# small_tv.net
KiCad netlist of a schematic drawn in EasyEDA Pro
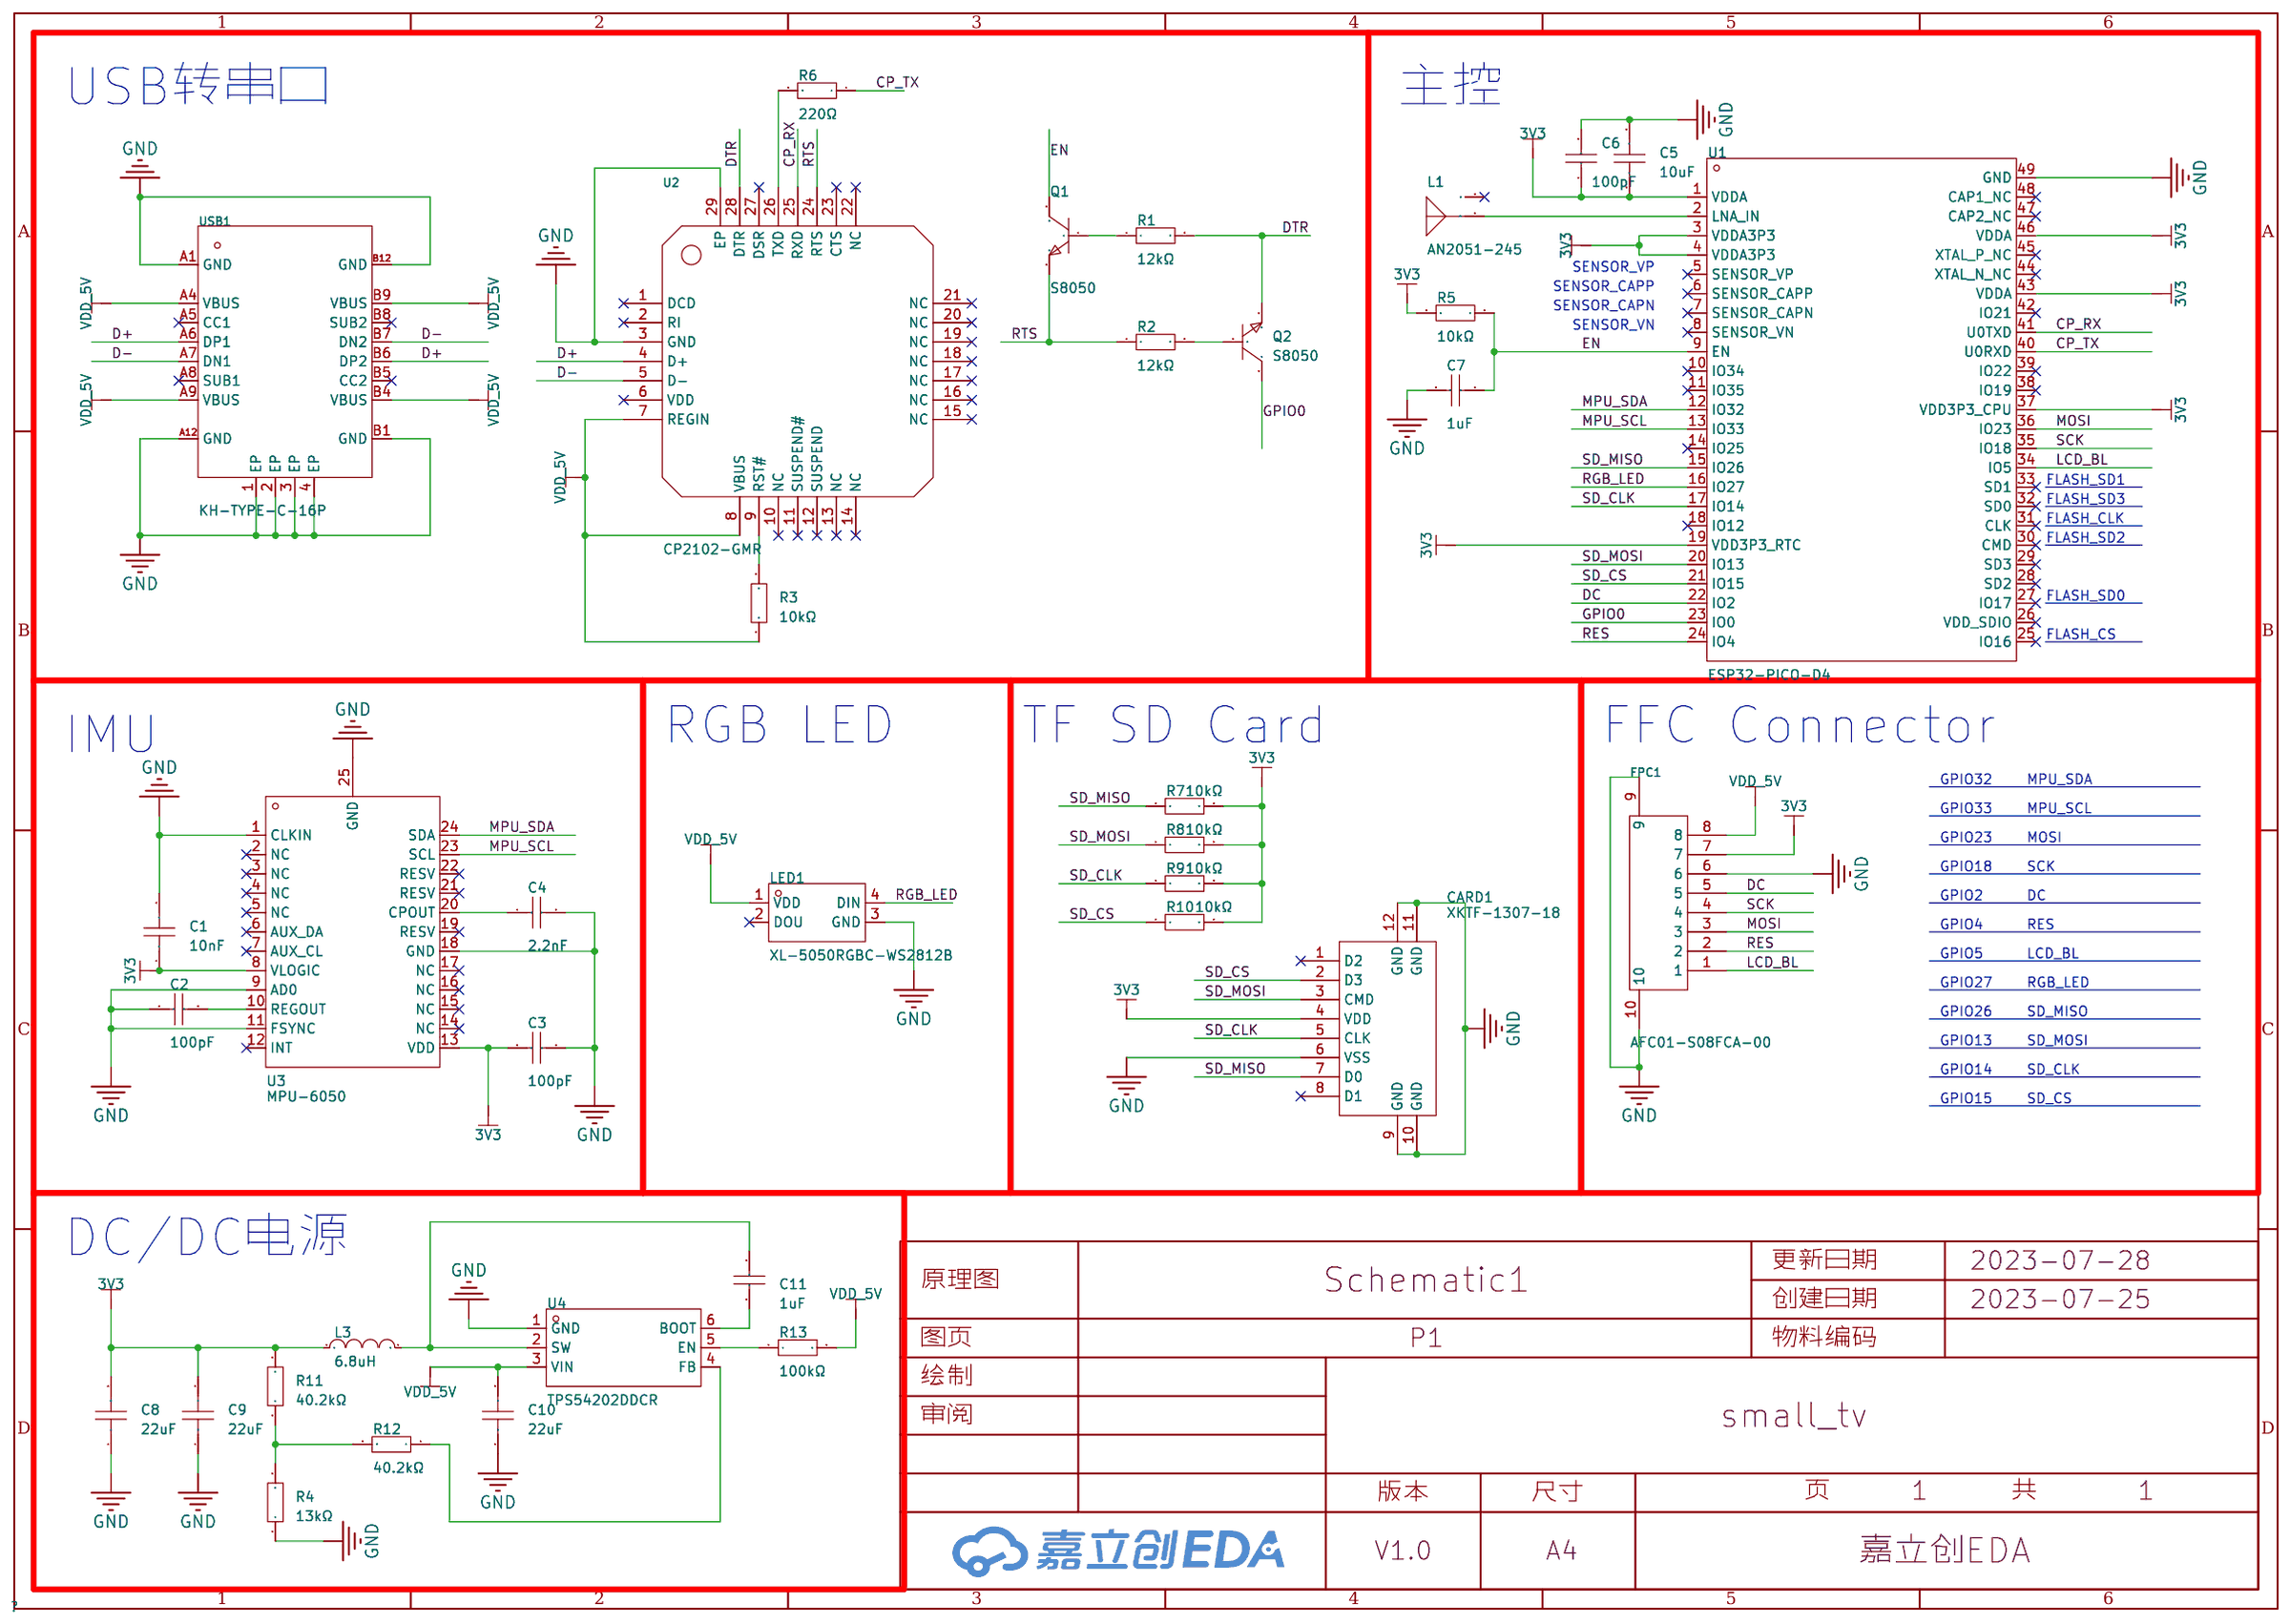
[diagram p0: schematic sheet]

(export (version "E")
  (design (tool "Eeschema 10.0.6"))
  (components
    (comp (ref "C1")
      (value "10nF")
      (footprint "easyedapro:C0603")
      (description "容值:10uF;精度:±10%;额定电压:10V;材质(温度系数):X5R;")
      (fields
        (field (name "Manufacturer Part") "CL10A106KP8NNNC")
        (field (name "Manufacturer") "SAMSUNG(三星)")
      )
      (libsource (lib "easyedapro") (part "CL10A106KP8NNNC"))
    )
    (comp (ref "C2")
      (value "100pF")
      (footprint "easyedapro:C0603")
      (description "容值:100pF;精度:±5%;额定电压:50V;材质(温度系数):C0G;")
      (fields
        (field (name "Manufacturer Part") "CL10C101JB8NNNC")
        (field (name "Manufacturer") "SAMSUNG(三星)")
      )
      (libsource (lib "easyedapro") (part "CL10C101JB8NNNC"))
    )
    (comp (ref "C3")
      (value "100pF")
      (footprint "easyedapro:C0603")
      (description "容值:100pF;精度:±5%;额定电压:50V;材质(温度系数):C0G;")
      (fields
        (field (name "Manufacturer Part") "CL10C101JB8NNNC")
        (field (name "Manufacturer") "SAMSUNG(三星)")
      )
      (libsource (lib "easyedapro") (part "CL10C101JB8NNNC"))
    )
    (comp (ref "C4")
      (value "2.2nF")
      (footprint "easyedapro:C0603")
      (description "容值:2.2nF;精度:±5%;额定电压:50V;材质(温度系数):NP0;")
      (fields
        (field (name "Manufacturer Part") "CC0603JRNPO9BN222")
        (field (name "Manufacturer") "YAGEO(国巨)")
      )
      (libsource (lib "easyedapro") (part "CC0603JRNPO9BN222"))
    )
    (comp (ref "C5")
      (value "10uF")
      (footprint "easyedapro:C0603")
      (description "容值:10uF;精度:±10%;额定电压:10V;材质(温度系数):X5R;")
      (fields
        (field (name "Manufacturer Part") "CL10A106KP8NNNC")
        (field (name "Manufacturer") "SAMSUNG(三星)")
      )
      (libsource (lib "easyedapro") (part "CL10A106KP8NNNC"))
    )
    (comp (ref "C6")
      (value "100pF")
      (footprint "easyedapro:C0603")
      (description "容值:100pF;精度:±5%;额定电压:50V;材质(温度系数):C0G;")
      (fields
        (field (name "Manufacturer Part") "CL10C101JB8NNNC")
        (field (name "Manufacturer") "SAMSUNG(三星)")
      )
      (libsource (lib "easyedapro") (part "CL10C101JB8NNNC"))
    )
    (comp (ref "C7")
      (value "1uF")
      (footprint "easyedapro:C0603")
      (description "容值:1uF;精度:±10%;额定电压:50V;材质(温度系数):X5R;")
      (fields
        (field (name "Manufacturer Part") "CL10A105KB8NNNC")
        (field (name "Manufacturer") "SAMSUNG(三星)")
      )
      (libsource (lib "easyedapro") (part "CL10A105KB8NNNC"))
    )
    (comp (ref "C8")
      (value "22uF")
      (footprint "easyedapro:C0603")
      (description "容值:22uF;精度:±20%;额定电压:10V;材质(温度系数):X5R;")
      (fields
        (field (name "Manufacturer Part") "CL10A226MP8NUNE")
        (field (name "Manufacturer") "SAMSUNG(三星)")
      )
      (libsource (lib "easyedapro") (part "CL10A226MP8NUNE"))
    )
    (comp (ref "C9")
      (value "22uF")
      (footprint "easyedapro:C0603")
      (description "容值:22uF;精度:±20%;额定电压:10V;材质(温度系数):X5R;")
      (fields
        (field (name "Manufacturer Part") "CL10A226MP8NUNE")
        (field (name "Manufacturer") "SAMSUNG(三星)")
      )
      (libsource (lib "easyedapro") (part "CL10A226MP8NUNE"))
    )
    (comp (ref "C10")
      (value "22uF")
      (footprint "easyedapro:C0603")
      (description "容值:22uF;精度:±20%;额定电压:10V;材质(温度系数):X5R;")
      (fields
        (field (name "Manufacturer Part") "CL10A226MP8NUNE")
        (field (name "Manufacturer") "SAMSUNG(三星)")
      )
      (libsource (lib "easyedapro") (part "CL10A226MP8NUNE"))
    )
    (comp (ref "C11")
      (value "1uF")
      (footprint "easyedapro:C0603")
      (description "容值:1uF;精度:±10%;额定电压:50V;材质(温度系数):X5R;")
      (fields
        (field (name "Manufacturer Part") "CL10A105KB8NNNC")
        (field (name "Manufacturer") "SAMSUNG(三星)")
      )
      (libsource (lib "easyedapro") (part "CL10A105KB8NNNC"))
    )
    (comp (ref "CARD1")
      (value "XKTF-1307-18")
      (footprint "easyedapro:TF-SMD_XKTF-1307-18")
      (fields (field (name "Manufacturer") "XKB Connectivity(中国星坤)"))
      (libsource (lib "easyedapro") (part "XKTF-1307-18"))
    )
    (comp (ref "FPC1")
      (value "AFC01-S08FCA-00")
      (footprint "easyedapro:FPC-SMD_P0.50-8P_FGS-XJ-H2.0")
      (description "间距:0.5mm;触点数量:8P;锁定特性:翻盖式;安装类型:卧贴;触点类型:下接;")
      (fields (field (name "Manufacturer") "JS(钜硕电子)"))
      (libsource (lib "easyedapro") (part "AFC01-S08FCA-00"))
    )
    (comp (ref "L1")
      (value "AN2051-245")
      (footprint "easyedapro:ANT2051")
      (description "小体积，高增益，WIFI，蓝牙，zigBee 2.4G天线")
      (fields (field (name "Manufacturer") "rainsun(霖昱微)"))
      (libsource (lib "easyedapro") (part "AN2051-245"))
    )
    (comp (ref "L3")
      (value "6.8uH")
      (footprint "easyedapro:IND-SMD_L4.4-W4.2")
      (description "电感值:6.8uH;精度:±20%;额定电流:2.4A;饱和电流(Isat):2.5A;")
      (fields (field (name "Manufacturer Part") "FXL0420-6R8-M") (field (name "Manufacturer") "cjiang(长江微电)"))
      (libsource (lib "easyedapro") (part "FXL0420-6R8-M"))
    )
    (comp (ref "LED1")
      (value "XL-5050RGBC-WS2812B")
      (footprint "easyedapro:LED-SMD_4P-L5.0-W5.0-BL_XL-5050RGBC")
      (description "发光颜色:RGB三色;二极管配置:-;主波长:-;色温:-;功率:-;安装方式:正贴;")
      (fields (field (name "Manufacturer") "XINGLIGHT(成兴光)"))
      (libsource (lib "easyedapro") (part "XL-5050RGBC-WS2812B"))
    )
    (comp (ref "Q1")
      (value "S8050")
      (footprint "easyedapro:SOT-23-3_L2.9-W1.6-P1.90-LS2.8-BR")
      (description "晶体管类型:NPN;集射极击穿电压(Vceo):25V;集电极电流(Ic):500mA;功率(Pd):300mW;直流电流增益(hFE@Ic,Vce):120@50mA,1V;")
      (fields (field (name "Manufacturer") "CJ(江苏长电/长晶)"))
      (libsource (lib "easyedapro") (part "S8050_C105433"))
    )
    (comp (ref "Q2")
      (value "S8050")
      (footprint "easyedapro:SOT-23-3_L2.9-W1.6-P1.90-LS2.8-BR")
      (description "晶体管类型:NPN;集射极击穿电压(Vceo):25V;集电极电流(Ic):500mA;功率(Pd):300mW;直流电流增益(hFE@Ic,Vce):120@50mA,1V;")
      (fields (field (name "Manufacturer") "CJ(江苏长电/长晶)"))
      (libsource (lib "easyedapro") (part "S8050_C105433"))
    )
    (comp (ref "R1")
      (value "12kΩ")
      (footprint "easyedapro:R0603")
      (description "电阻类型:厚膜电阻;阻值:12kΩ;精度:±1%;功率:100mW;")
      (fields
        (field (name "Manufacturer Part") "0603WAF1202T5E")
        (field (name "Manufacturer") "UNI-ROYAL(厚声)")
      )
      (libsource (lib "easyedapro") (part "0603WAF1202T5E"))
    )
    (comp (ref "R2")
      (value "12kΩ")
      (footprint "easyedapro:R0603")
      (description "电阻类型:厚膜电阻;阻值:12kΩ;精度:±1%;功率:100mW;")
      (fields
        (field (name "Manufacturer Part") "0603WAF1202T5E")
        (field (name "Manufacturer") "UNI-ROYAL(厚声)")
      )
      (libsource (lib "easyedapro") (part "0603WAF1202T5E"))
    )
    (comp (ref "R3")
      (value "10kΩ")
      (footprint "easyedapro:R0603")
      (description "电阻类型:厚膜电阻;阻值:10kΩ;精度:±1%;功率:100mW;")
      (fields
        (field (name "Manufacturer Part") "0603WAF1002T5E")
        (field (name "Manufacturer") "UNI-ROYAL(厚声)")
      )
      (libsource (lib "easyedapro") (part "0603WAF1002T5E"))
    )
    (comp (ref "R4")
      (value "13kΩ")
      (footprint "easyedapro:R0603")
      (description "电阻类型:厚膜电阻;阻值:13kΩ;精度:±1%;功率:100mW;")
      (fields
        (field (name "Manufacturer Part") "0603WAF1302T5E")
        (field (name "Manufacturer") "UNI-ROYAL(厚声)")
      )
      (libsource (lib "easyedapro") (part "0603WAF1302T5E"))
    )
    (comp (ref "R5")
      (value "10kΩ")
      (footprint "easyedapro:R0603")
      (description "电阻类型:厚膜电阻;阻值:10kΩ;精度:±1%;功率:100mW;")
      (fields
        (field (name "Manufacturer Part") "0603WAF1002T5E")
        (field (name "Manufacturer") "UNI-ROYAL(厚声)")
      )
      (libsource (lib "easyedapro") (part "0603WAF1002T5E"))
    )
    (comp (ref "R6")
      (value "220Ω")
      (footprint "easyedapro:R0603")
      (description "电阻类型:厚膜电阻;阻值:220Ω;精度:±1%;功率:100mW;")
      (fields
        (field (name "Manufacturer Part") "0603WAF2200T5E")
        (field (name "Manufacturer") "UNI-ROYAL(厚声)")
      )
      (libsource (lib "easyedapro") (part "0603WAF2200T5E"))
    )
    (comp (ref "R7")
      (value "10kΩ")
      (footprint "easyedapro:R0603")
      (description "电阻类型:厚膜电阻;阻值:10kΩ;精度:±1%;功率:100mW;")
      (fields
        (field (name "Manufacturer Part") "0603WAF1002T5E")
        (field (name "Manufacturer") "UNI-ROYAL(厚声)")
      )
      (libsource (lib "easyedapro") (part "0603WAF1002T5E"))
    )
    (comp (ref "R8")
      (value "10kΩ")
      (footprint "easyedapro:R0603")
      (description "电阻类型:厚膜电阻;阻值:10kΩ;精度:±1%;功率:100mW;")
      (fields
        (field (name "Manufacturer Part") "0603WAF1002T5E")
        (field (name "Manufacturer") "UNI-ROYAL(厚声)")
      )
      (libsource (lib "easyedapro") (part "0603WAF1002T5E"))
    )
    (comp (ref "R9")
      (value "10kΩ")
      (footprint "easyedapro:R0603")
      (description "电阻类型:厚膜电阻;阻值:10kΩ;精度:±1%;功率:100mW;")
      (fields
        (field (name "Manufacturer Part") "0603WAF1002T5E")
        (field (name "Manufacturer") "UNI-ROYAL(厚声)")
      )
      (libsource (lib "easyedapro") (part "0603WAF1002T5E"))
    )
    (comp (ref "R10")
      (value "10kΩ")
      (footprint "easyedapro:R0603")
      (description "电阻类型:厚膜电阻;阻值:10kΩ;精度:±1%;功率:100mW;")
      (fields
        (field (name "Manufacturer Part") "0603WAF1002T5E")
        (field (name "Manufacturer") "UNI-ROYAL(厚声)")
      )
      (libsource (lib "easyedapro") (part "0603WAF1002T5E"))
    )
    (comp (ref "R11")
      (value "40.2kΩ")
      (footprint "easyedapro:R0603")
      (description "电阻类型:厚膜电阻;阻值:40.2kΩ;精度:±1%;功率:100mW;")
      (fields
        (field (name "Manufacturer Part") "0603WAF4022T5E")
        (field (name "Manufacturer") "UNI-ROYAL(厚声)")
      )
      (libsource (lib "easyedapro") (part "0603WAF4022T5E"))
    )
    (comp (ref "R12")
      (value "40.2kΩ")
      (footprint "easyedapro:R0603")
      (description "电阻类型:厚膜电阻;阻值:40.2kΩ;精度:±1%;功率:100mW;")
      (fields
        (field (name "Manufacturer Part") "0603WAF4022T5E")
        (field (name "Manufacturer") "UNI-ROYAL(厚声)")
      )
      (libsource (lib "easyedapro") (part "0603WAF4022T5E"))
    )
    (comp (ref "R13")
      (value "100kΩ")
      (footprint "easyedapro:R0603")
      (description "电阻类型:厚膜电阻;阻值:100kΩ;精度:±1%;功率:100mW;")
      (fields
        (field (name "Manufacturer Part") "0603WAF1003T5E")
        (field (name "Manufacturer") "UNI-ROYAL(厚声)")
      )
      (libsource (lib "easyedapro") (part "0603WAF1003T5E"))
    )
    (comp (ref "U1")
      (value "ESP32-PICO-D4")
      (footprint "easyedapro:LGA-48_L7.0-W7.0-P0.50-BL-EP5.4")
      (fields (field (name "Manufacturer") "ESPRESSIF(乐鑫)"))
      (libsource (lib "easyedapro") (part "ESP32-PICO-D4"))
    )
    (comp (ref "U2")
      (value "CP2102-GMR")
      (footprint "easyedapro:WQFN-28_L5.0-W5.0-P0.50-BL-EP3.2")
      (description "应用功能:收发器;接口协议:USB;数据速率:1Mbps;")
      (fields (field (name "Manufacturer") "SILICON LABS(芯科)"))
      (libsource (lib "easyedapro") (part "CP2102-GMR"))
    )
    (comp (ref "U3")
      (value "MPU-6050")
      (footprint "easyedapro:QFN-24_L4.0-W4.0-P0.50-BL-EP2.7")
      (description "三轴加速度计和三轴陀螺仪，工作电压：2.375V~3.46V")
      (fields (field (name "Manufacturer") "TDK InvenSense(应美盛)"))
      (libsource (lib "easyedapro") (part "MPU-6050_C24112"))
    )
    (comp (ref "U4")
      (value "TPS54202DDCR")
      (footprint "easyedapro:SOT-23-6_L2.9-W1.6-P0.95-LS2.8-BL")
      (description "可输出电流:2A;开关工作频率:500kHz;输出类型:Adjustable;输出电压的路数:1;功能类型:Step-Down;输出配置:Positive;")
      (fields (field (name "Manufacturer") "TI(德州仪器)"))
      (libsource (lib "easyedapro") (part "TPS54202DDCR"))
    )
    (comp (ref "USB1")
      (value "KH-TYPE-C-16P")
      (footprint "easyedapro:USB-C-SMD_KH-TYPE-C-16P")
      (description "Type-C母座 16PIN 立式四角贴板无压片")
      (fields (field (name "Manufacturer") "kinghelm(金航标)"))
      (libsource (lib "easyedapro") (part "KH-TYPE-C-16P"))
    )
  )
  (nets
    (net (code "1") (name "/CP_RX") (class "Default")
      (node (ref "U1") (pin "41") (pinfunction "U0TXD_41") (pintype "input"))
      (node (ref "U2") (pin "25") (pinfunction "RXD_25") (pintype "input"))
    )
    (net (code "2") (name "/CP_TX") (class "Default")
      (node (ref "R6") (pin "1") (pinfunction "1_1") (pintype "input"))
      (node (ref "U1") (pin "40") (pinfunction "U0RXD_40") (pintype "input"))
    )
    (net (code "3") (name "/D+") (class "Default")
      (node (ref "U2") (pin "4") (pinfunction "D+_4") (pintype "input"))
      (node (ref "USB1") (pin "A6") (pinfunction "DP1_A6") (pintype "input"))
      (node (ref "USB1") (pin "B6") (pinfunction "DP2_B6") (pintype "input"))
    )
    (net (code "4") (name "/D-") (class "Default")
      (node (ref "U2") (pin "5") (pinfunction "D-_5") (pintype "input"))
      (node (ref "USB1") (pin "A7") (pinfunction "DN1_A7") (pintype "input"))
      (node (ref "USB1") (pin "B7") (pinfunction "DN2_B7") (pintype "input"))
    )
    (net (code "5") (name "/DC") (class "Default")
      (node (ref "FPC1") (pin "5") (pinfunction "5_5") (pintype "input"))
      (node (ref "U1") (pin "22") (pinfunction "IO2_22") (pintype "input"))
    )
    (net (code "6") (name "/DTR") (class "Default")
      (node (ref "Q2") (pin "2") (pinfunction "2_2") (pintype "input"))
      (node (ref "R1") (pin "2") (pinfunction "2_2") (pintype "input"))
      (node (ref "U2") (pin "28") (pinfunction "DTR_28") (pintype "input"))
    )
    (net (code "7") (name "/EN") (class "Default")
      (node (ref "C7") (pin "1") (pinfunction "1_1") (pintype "input"))
      (node (ref "Q1") (pin "3") (pinfunction "3_3") (pintype "input"))
      (node (ref "R5") (pin "1") (pinfunction "1_1") (pintype "input"))
      (node (ref "U1") (pin "9") (pinfunction "EN_9") (pintype "input"))
    )
    (net (code "8") (name "/GPIO0") (class "Default")
      (node (ref "Q2") (pin "3") (pinfunction "3_3") (pintype "input"))
      (node (ref "U1") (pin "23") (pinfunction "IO0_23") (pintype "input"))
    )
    (net (code "9") (name "/LCD_BL") (class "Default")
      (node (ref "FPC1") (pin "1") (pinfunction "1_1") (pintype "input"))
      (node (ref "U1") (pin "34") (pinfunction "IO5_34") (pintype "input"))
    )
    (net (code "10") (name "/MOSI") (class "Default")
      (node (ref "FPC1") (pin "3") (pinfunction "3_3") (pintype "input"))
      (node (ref "U1") (pin "36") (pinfunction "IO23_36") (pintype "input"))
    )
    (net (code "11") (name "/MPU_SCL") (class "Default")
      (node (ref "U1") (pin "13") (pinfunction "IO33_13") (pintype "input"))
      (node (ref "U3") (pin "23") (pinfunction "SCL_23") (pintype "input"))
    )
    (net (code "12") (name "/MPU_SDA") (class "Default")
      (node (ref "U1") (pin "12") (pinfunction "IO32_12") (pintype "input"))
      (node (ref "U3") (pin "24") (pinfunction "SDA_24") (pintype "input"))
    )
    (net (code "13") (name "/RES") (class "Default")
      (node (ref "FPC1") (pin "2") (pinfunction "2_2") (pintype "input"))
      (node (ref "U1") (pin "24") (pinfunction "IO4_24") (pintype "input"))
    )
    (net (code "14") (name "/RGB_LED") (class "Default")
      (node (ref "LED1") (pin "4") (pinfunction "DIN_4") (pintype "input"))
      (node (ref "U1") (pin "16") (pinfunction "IO27_16") (pintype "input"))
    )
    (net (code "15") (name "/RTS") (class "Default")
      (node (ref "Q1") (pin "2") (pinfunction "2_2") (pintype "input"))
      (node (ref "R2") (pin "1") (pinfunction "1_1") (pintype "input"))
      (node (ref "U2") (pin "24") (pinfunction "RTS_24") (pintype "input"))
    )
    (net (code "16") (name "/SCK") (class "Default")
      (node (ref "FPC1") (pin "4") (pinfunction "4_4") (pintype "input"))
      (node (ref "U1") (pin "35") (pinfunction "IO18_35") (pintype "input"))
    )
    (net (code "17") (name "/SD_CLK") (class "Default")
      (node (ref "CARD1") (pin "5") (pinfunction "CLK_5") (pintype "input"))
      (node (ref "R9") (pin "1") (pinfunction "1_1") (pintype "input"))
      (node (ref "U1") (pin "17") (pinfunction "IO14_17") (pintype "input"))
    )
    (net (code "18") (name "/SD_CS") (class "Default")
      (node (ref "CARD1") (pin "2") (pinfunction "D3_2") (pintype "input"))
      (node (ref "R10") (pin "1") (pinfunction "1_1") (pintype "input"))
      (node (ref "U1") (pin "21") (pinfunction "IO15_21") (pintype "input"))
    )
    (net (code "19") (name "/SD_MISO") (class "Default")
      (node (ref "CARD1") (pin "7") (pinfunction "D0_7") (pintype "input"))
      (node (ref "R7") (pin "1") (pinfunction "1_1") (pintype "input"))
      (node (ref "U1") (pin "15") (pinfunction "IO26_15") (pintype "input"))
    )
    (net (code "20") (name "/SD_MOSI") (class "Default")
      (node (ref "CARD1") (pin "3") (pinfunction "CMD_3") (pintype "input"))
      (node (ref "R8") (pin "1") (pinfunction "1_1") (pintype "input"))
      (node (ref "U1") (pin "20") (pinfunction "IO13_20") (pintype "input"))
    )
    (net (code "21") (name "3V3") (class "Default")
      (node (ref "C1") (pin "1") (pinfunction "1_1") (pintype "input"))
      (node (ref "C3") (pin "1") (pinfunction "1_1") (pintype "input"))
      (node (ref "C5") (pin "1") (pinfunction "1_1") (pintype "input"))
      (node (ref "C6") (pin "1") (pinfunction "1_1") (pintype "input"))
      (node (ref "C8") (pin "2") (pinfunction "2_2") (pintype "input"))
      (node (ref "C9") (pin "2") (pinfunction "2_2") (pintype "input"))
      (node (ref "CARD1") (pin "4") (pinfunction "VDD_4") (pintype "input"))
      (node (ref "FPC1") (pin "7") (pinfunction "7_7") (pintype "input"))
      (node (ref "L3") (pin "1") (pinfunction "1_1") (pintype "input"))
      (node (ref "R10") (pin "2") (pinfunction "2_2") (pintype "input"))
      (node (ref "R11") (pin "2") (pinfunction "2_2") (pintype "input"))
      (node (ref "R5") (pin "2") (pinfunction "2_2") (pintype "input"))
      (node (ref "R7") (pin "2") (pinfunction "2_2") (pintype "input"))
      (node (ref "R8") (pin "2") (pinfunction "2_2") (pintype "input"))
      (node (ref "R9") (pin "2") (pinfunction "2_2") (pintype "input"))
      (node (ref "U1") (pin "1") (pinfunction "VDDA_1") (pintype "input"))
      (node (ref "U1") (pin "19") (pinfunction "VDD3P3_RTC_19") (pintype "input"))
      (node (ref "U1") (pin "3") (pinfunction "VDDA3P3_3") (pintype "input"))
      (node (ref "U1") (pin "37") (pinfunction "VDD3P3_CPU_37") (pintype "input"))
      (node (ref "U1") (pin "4") (pinfunction "VDDA3P3_4") (pintype "input"))
      (node (ref "U1") (pin "43") (pinfunction "VDDA_43") (pintype "input"))
      (node (ref "U1") (pin "46") (pinfunction "VDDA_46") (pintype "input"))
      (node (ref "U3") (pin "13") (pinfunction "VDD_13") (pintype "input"))
      (node (ref "U3") (pin "8") (pinfunction "VLOGIC_8") (pintype "input"))
    )
    (net (code "22") (name "GND") (class "Default")
      (node (ref "C1") (pin "2") (pinfunction "2_2") (pintype "input"))
      (node (ref "C10") (pin "1") (pinfunction "1_1") (pintype "input"))
      (node (ref "C2") (pin "1") (pinfunction "1_1") (pintype "input"))
      (node (ref "C3") (pin "2") (pinfunction "2_2") (pintype "input"))
      (node (ref "C4") (pin "2") (pinfunction "2_2") (pintype "input"))
      (node (ref "C5") (pin "2") (pinfunction "2_2") (pintype "input"))
      (node (ref "C6") (pin "2") (pinfunction "2_2") (pintype "input"))
      (node (ref "C7") (pin "2") (pinfunction "2_2") (pintype "input"))
      (node (ref "C8") (pin "1") (pinfunction "1_1") (pintype "input"))
      (node (ref "C9") (pin "1") (pinfunction "1_1") (pintype "input"))
      (node (ref "CARD1") (pin "10") (pinfunction "GND_10") (pintype "input"))
      (node (ref "CARD1") (pin "11") (pinfunction "GND_11") (pintype "input"))
      (node (ref "CARD1") (pin "12") (pinfunction "GND_12") (pintype "input"))
      (node (ref "CARD1") (pin "6") (pinfunction "VSS_6") (pintype "input"))
      (node (ref "CARD1") (pin "9") (pinfunction "GND_9") (pintype "input"))
      (node (ref "FPC1") (pin "10") (pinfunction "10_10") (pintype "input"))
      (node (ref "FPC1") (pin "6") (pinfunction "6_6") (pintype "input"))
      (node (ref "FPC1") (pin "9") (pinfunction "9_9") (pintype "input"))
      (node (ref "LED1") (pin "3") (pinfunction "GND_3") (pintype "input"))
      (node (ref "R4") (pin "1") (pinfunction "1_1") (pintype "input"))
      (node (ref "U1") (pin "49") (pinfunction "GND_49") (pintype "input"))
      (node (ref "U2") (pin "29") (pinfunction "EP_29") (pintype "input"))
      (node (ref "U2") (pin "3") (pinfunction "GND_3") (pintype "input"))
      (node (ref "U3") (pin "1") (pinfunction "CLKIN_1") (pintype "input"))
      (node (ref "U3") (pin "11") (pinfunction "FSYNC_11") (pintype "input"))
      (node (ref "U3") (pin "18") (pinfunction "GND_18") (pintype "input"))
      (node (ref "U3") (pin "25") (pinfunction "GND_25") (pintype "input"))
      (node (ref "U3") (pin "9") (pinfunction "AD0_9") (pintype "input"))
      (node (ref "U4") (pin "1") (pinfunction "GND_1") (pintype "input"))
      (node (ref "USB1") (pin "1") (pinfunction "EP_1") (pintype "input"))
      (node (ref "USB1") (pin "2") (pinfunction "EP_2") (pintype "input"))
      (node (ref "USB1") (pin "3") (pinfunction "EP_3") (pintype "input"))
      (node (ref "USB1") (pin "4") (pinfunction "EP_4") (pintype "input"))
      (node (ref "USB1") (pin "A1") (pinfunction "GND_A1") (pintype "input"))
      (node (ref "USB1") (pin "A12") (pinfunction "GND_A12") (pintype "input"))
      (node (ref "USB1") (pin "B1") (pinfunction "GND_B1") (pintype "input"))
      (node (ref "USB1") (pin "B12") (pinfunction "GND_B12") (pintype "input"))
    )
    (net (code "23") (name "Net-(L1-ANT)") (class "Default")
      (node (ref "L1") (pin "1") (pinfunction "ANT_1") (pintype "input"))
      (node (ref "U1") (pin "2") (pinfunction "LNA_IN_2") (pintype "input"))
    )
    (net (code "24") (name "Net-(Q1-Pad1)") (class "Default")
      (node (ref "Q1") (pin "1") (pinfunction "1_1") (pintype "input"))
      (node (ref "R1") (pin "1") (pinfunction "1_1") (pintype "input"))
    )
    (net (code "25") (name "Net-(Q2-Pad1)") (class "Default")
      (node (ref "Q2") (pin "1") (pinfunction "1_1") (pintype "input"))
      (node (ref "R2") (pin "2") (pinfunction "2_2") (pintype "input"))
    )
    (net (code "26") (name "Net-(R11-Pad1)") (class "Default")
      (node (ref "R11") (pin "1") (pinfunction "1_1") (pintype "input"))
      (node (ref "R12") (pin "2") (pinfunction "2_2") (pintype "input"))
      (node (ref "R4") (pin "2") (pinfunction "2_2") (pintype "input"))
    )
    (net (code "27") (name "Net-(U2-RST#)") (class "Default")
      (node (ref "R3") (pin "2") (pinfunction "2_2") (pintype "input"))
      (node (ref "U2") (pin "9") (pinfunction "RST#_9") (pintype "input"))
    )
    (net (code "28") (name "Net-(U2-TXD)") (class "Default")
      (node (ref "R6") (pin "2") (pinfunction "2_2") (pintype "input"))
      (node (ref "U2") (pin "26") (pinfunction "TXD_26") (pintype "input"))
    )
    (net (code "29") (name "Net-(U3-CPOUT)") (class "Default")
      (node (ref "C4") (pin "1") (pinfunction "1_1") (pintype "input"))
      (node (ref "U3") (pin "20") (pinfunction "CPOUT_20") (pintype "input"))
    )
    (net (code "30") (name "Net-(U3-REGOUT)") (class "Default")
      (node (ref "C2") (pin "2") (pinfunction "2_2") (pintype "input"))
      (node (ref "U3") (pin "10") (pinfunction "REGOUT_10") (pintype "input"))
    )
    (net (code "31") (name "Net-(U4-BOOT)") (class "Default")
      (node (ref "C11") (pin "1") (pinfunction "1_1") (pintype "input"))
      (node (ref "U4") (pin "6") (pinfunction "BOOT_6") (pintype "input"))
    )
    (net (code "32") (name "Net-(U4-EN)") (class "Default")
      (node (ref "R13") (pin "1") (pinfunction "1_1") (pintype "input"))
      (node (ref "U4") (pin "5") (pinfunction "EN_5") (pintype "input"))
    )
    (net (code "33") (name "Net-(U4-FB)") (class "Default")
      (node (ref "R12") (pin "1") (pinfunction "1_1") (pintype "input"))
      (node (ref "U4") (pin "4") (pinfunction "FB_4") (pintype "input"))
    )
    (net (code "34") (name "Net-(U4-SW)") (class "Default")
      (node (ref "C11") (pin "2") (pinfunction "2_2") (pintype "input"))
      (node (ref "L3") (pin "2") (pinfunction "2_2") (pintype "input"))
      (node (ref "U4") (pin "2") (pinfunction "SW_2") (pintype "input"))
    )
    (net (code "35") (name "VDD_5V") (class "Default")
      (node (ref "C10") (pin "2") (pinfunction "2_2") (pintype "input"))
      (node (ref "FPC1") (pin "8") (pinfunction "8_8") (pintype "input"))
      (node (ref "LED1") (pin "1") (pinfunction "VDD_1") (pintype "input"))
      (node (ref "R13") (pin "2") (pinfunction "2_2") (pintype "input"))
      (node (ref "R3") (pin "1") (pinfunction "1_1") (pintype "input"))
      (node (ref "U2") (pin "7") (pinfunction "REGIN_7") (pintype "input"))
      (node (ref "U2") (pin "8") (pinfunction "VBUS_8") (pintype "input"))
      (node (ref "U4") (pin "3") (pinfunction "VIN_3") (pintype "input"))
      (node (ref "USB1") (pin "A4") (pinfunction "VBUS_A4") (pintype "input"))
      (node (ref "USB1") (pin "A9") (pinfunction "VBUS_A9") (pintype "input"))
      (node (ref "USB1") (pin "B4") (pinfunction "VBUS_B4") (pintype "input"))
      (node (ref "USB1") (pin "B9") (pinfunction "VBUS_B9") (pintype "input"))
    )
    (net (code "36") (name "unconnected-(CARD1-D1-Pad8)") (class "Default")
      (node (ref "CARD1") (pin "8") (pinfunction "D1_8") (pintype "input+no_connect"))
    )
    (net (code "37") (name "unconnected-(CARD1-D2-Pad1)") (class "Default")
      (node (ref "CARD1") (pin "1") (pinfunction "D2_1") (pintype "input+no_connect"))
    )
    (net (code "38") (name "unconnected-(L1-Pad2)") (class "Default")
      (node (ref "L1") (pin "2") (pinfunction "2_2") (pintype "input+no_connect"))
    )
    (net (code "39") (name "unconnected-(LED1-DOU-Pad2)") (class "Default")
      (node (ref "LED1") (pin "2") (pinfunction "DOU_2") (pintype "input+no_connect"))
    )
    (net (code "40") (name "unconnected-(U1-CAP1_NC-Pad48)") (class "Default")
      (node (ref "U1") (pin "48") (pinfunction "CAP1_NC_48") (pintype "input+no_connect"))
    )
    (net (code "41") (name "unconnected-(U1-CAP2_NC-Pad47)") (class "Default")
      (node (ref "U1") (pin "47") (pinfunction "CAP2_NC_47") (pintype "input+no_connect"))
    )
    (net (code "42") (name "unconnected-(U1-CLK-Pad31)") (class "Default")
      (node (ref "U1") (pin "31") (pinfunction "CLK_31") (pintype "input+no_connect"))
    )
    (net (code "43") (name "unconnected-(U1-CMD-Pad30)") (class "Default")
      (node (ref "U1") (pin "30") (pinfunction "CMD_30") (pintype "input+no_connect"))
    )
    (net (code "44") (name "unconnected-(U1-IO12-Pad18)") (class "Default")
      (node (ref "U1") (pin "18") (pinfunction "IO12_18") (pintype "input+no_connect"))
    )
    (net (code "45") (name "unconnected-(U1-IO16-Pad25)") (class "Default")
      (node (ref "U1") (pin "25") (pinfunction "IO16_25") (pintype "input+no_connect"))
    )
    (net (code "46") (name "unconnected-(U1-IO17-Pad27)") (class "Default")
      (node (ref "U1") (pin "27") (pinfunction "IO17_27") (pintype "input+no_connect"))
    )
    (net (code "47") (name "unconnected-(U1-IO19-Pad38)") (class "Default")
      (node (ref "U1") (pin "38") (pinfunction "IO19_38") (pintype "input+no_connect"))
    )
    (net (code "48") (name "unconnected-(U1-IO21-Pad42)") (class "Default")
      (node (ref "U1") (pin "42") (pinfunction "IO21_42") (pintype "input+no_connect"))
    )
    (net (code "49") (name "unconnected-(U1-IO22-Pad39)") (class "Default")
      (node (ref "U1") (pin "39") (pinfunction "IO22_39") (pintype "input+no_connect"))
    )
    (net (code "50") (name "unconnected-(U1-IO25-Pad14)") (class "Default")
      (node (ref "U1") (pin "14") (pinfunction "IO25_14") (pintype "input+no_connect"))
    )
    (net (code "51") (name "unconnected-(U1-IO34-Pad10)") (class "Default")
      (node (ref "U1") (pin "10") (pinfunction "IO34_10") (pintype "input+no_connect"))
    )
    (net (code "52") (name "unconnected-(U1-IO35-Pad11)") (class "Default")
      (node (ref "U1") (pin "11") (pinfunction "IO35_11") (pintype "input+no_connect"))
    )
    (net (code "53") (name "unconnected-(U1-SD0-Pad32)") (class "Default")
      (node (ref "U1") (pin "32") (pinfunction "SD0_32") (pintype "input+no_connect"))
    )
    (net (code "54") (name "unconnected-(U1-SD1-Pad33)") (class "Default")
      (node (ref "U1") (pin "33") (pinfunction "SD1_33") (pintype "input+no_connect"))
    )
    (net (code "55") (name "unconnected-(U1-SD2-Pad28)") (class "Default")
      (node (ref "U1") (pin "28") (pinfunction "SD2_28") (pintype "input+no_connect"))
    )
    (net (code "56") (name "unconnected-(U1-SD3-Pad29)") (class "Default")
      (node (ref "U1") (pin "29") (pinfunction "SD3_29") (pintype "input+no_connect"))
    )
    (net (code "57") (name "unconnected-(U1-SENSOR_CAPN-Pad7)") (class "Default")
      (node (ref "U1") (pin "7") (pinfunction "SENSOR_CAPN_7") (pintype "input+no_connect"))
    )
    (net (code "58") (name "unconnected-(U1-SENSOR_CAPP-Pad6)") (class "Default")
      (node (ref "U1") (pin "6") (pinfunction "SENSOR_CAPP_6") (pintype "input+no_connect"))
    )
    (net (code "59") (name "unconnected-(U1-SENSOR_VN-Pad8)") (class "Default")
      (node (ref "U1") (pin "8") (pinfunction "SENSOR_VN_8") (pintype "input+no_connect"))
    )
    (net (code "60") (name "unconnected-(U1-SENSOR_VP-Pad5)") (class "Default")
      (node (ref "U1") (pin "5") (pinfunction "SENSOR_VP_5") (pintype "input+no_connect"))
    )
    (net (code "61") (name "unconnected-(U1-VDD_SDIO-Pad26)") (class "Default")
      (node (ref "U1") (pin "26") (pinfunction "VDD_SDIO_26") (pintype "input+no_connect"))
    )
    (net (code "62") (name "unconnected-(U1-XTAL_N_NC-Pad44)") (class "Default")
      (node (ref "U1") (pin "44") (pinfunction "XTAL_N_NC_44") (pintype "input+no_connect"))
    )
    (net (code "63") (name "unconnected-(U1-XTAL_P_NC-Pad45)") (class "Default")
      (node (ref "U1") (pin "45") (pinfunction "XTAL_P_NC_45") (pintype "input+no_connect"))
    )
    (net (code "64") (name "unconnected-(U2-CTS-Pad23)") (class "Default")
      (node (ref "U2") (pin "23") (pinfunction "CTS_23") (pintype "input+no_connect"))
    )
    (net (code "65") (name "unconnected-(U2-DCD-Pad1)") (class "Default")
      (node (ref "U2") (pin "1") (pinfunction "DCD_1") (pintype "input+no_connect"))
    )
    (net (code "66") (name "unconnected-(U2-DSR-Pad27)") (class "Default")
      (node (ref "U2") (pin "27") (pinfunction "DSR_27") (pintype "input+no_connect"))
    )
    (net (code "67") (name "unconnected-(U2-NC-Pad10)") (class "Default")
      (node (ref "U2") (pin "10") (pinfunction "NC_10") (pintype "input+no_connect"))
    )
    (net (code "68") (name "unconnected-(U2-NC-Pad13)") (class "Default")
      (node (ref "U2") (pin "13") (pinfunction "NC_13") (pintype "input+no_connect"))
    )
    (net (code "69") (name "unconnected-(U2-NC-Pad14)") (class "Default")
      (node (ref "U2") (pin "14") (pinfunction "NC_14") (pintype "input+no_connect"))
    )
    (net (code "70") (name "unconnected-(U2-NC-Pad15)") (class "Default")
      (node (ref "U2") (pin "15") (pinfunction "NC_15") (pintype "input+no_connect"))
    )
    (net (code "71") (name "unconnected-(U2-NC-Pad16)") (class "Default")
      (node (ref "U2") (pin "16") (pinfunction "NC_16") (pintype "input+no_connect"))
    )
    (net (code "72") (name "unconnected-(U2-NC-Pad17)") (class "Default")
      (node (ref "U2") (pin "17") (pinfunction "NC_17") (pintype "input+no_connect"))
    )
    (net (code "73") (name "unconnected-(U2-NC-Pad18)") (class "Default")
      (node (ref "U2") (pin "18") (pinfunction "NC_18") (pintype "input+no_connect"))
    )
    (net (code "74") (name "unconnected-(U2-NC-Pad19)") (class "Default")
      (node (ref "U2") (pin "19") (pinfunction "NC_19") (pintype "input+no_connect"))
    )
    (net (code "75") (name "unconnected-(U2-NC-Pad20)") (class "Default")
      (node (ref "U2") (pin "20") (pinfunction "NC_20") (pintype "input+no_connect"))
    )
    (net (code "76") (name "unconnected-(U2-NC-Pad21)") (class "Default")
      (node (ref "U2") (pin "21") (pinfunction "NC_21") (pintype "input+no_connect"))
    )
    (net (code "77") (name "unconnected-(U2-NC-Pad22)") (class "Default")
      (node (ref "U2") (pin "22") (pinfunction "NC_22") (pintype "input+no_connect"))
    )
    (net (code "78") (name "unconnected-(U2-RI-Pad2)") (class "Default")
      (node (ref "U2") (pin "2") (pinfunction "RI_2") (pintype "input+no_connect"))
    )
    (net (code "79") (name "unconnected-(U2-SUSPEND#-Pad11)") (class "Default")
      (node (ref "U2") (pin "11") (pinfunction "SUSPEND#_11") (pintype "input+no_connect"))
    )
    (net (code "80") (name "unconnected-(U2-SUSPEND-Pad12)") (class "Default")
      (node (ref "U2") (pin "12") (pinfunction "SUSPEND_12") (pintype "input+no_connect"))
    )
    (net (code "81") (name "unconnected-(U2-VDD-Pad6)") (class "Default")
      (node (ref "U2") (pin "6") (pinfunction "VDD_6") (pintype "input+no_connect"))
    )
    (net (code "82") (name "unconnected-(U3-AUX_CL-Pad7)") (class "Default")
      (node (ref "U3") (pin "7") (pinfunction "AUX_CL_7") (pintype "input+no_connect"))
    )
    (net (code "83") (name "unconnected-(U3-AUX_DA-Pad6)") (class "Default")
      (node (ref "U3") (pin "6") (pinfunction "AUX_DA_6") (pintype "input+no_connect"))
    )
    (net (code "84") (name "unconnected-(U3-INT-Pad12)") (class "Default")
      (node (ref "U3") (pin "12") (pinfunction "INT_12") (pintype "input+no_connect"))
    )
    (net (code "85") (name "unconnected-(U3-NC-Pad2)") (class "Default")
      (node (ref "U3") (pin "2") (pinfunction "NC_2") (pintype "input+no_connect"))
    )
    (net (code "86") (name "unconnected-(U3-NC-Pad3)") (class "Default")
      (node (ref "U3") (pin "3") (pinfunction "NC_3") (pintype "input+no_connect"))
    )
    (net (code "87") (name "unconnected-(U3-NC-Pad4)") (class "Default")
      (node (ref "U3") (pin "4") (pinfunction "NC_4") (pintype "input+no_connect"))
    )
    (net (code "88") (name "unconnected-(U3-NC-Pad5)") (class "Default")
      (node (ref "U3") (pin "5") (pinfunction "NC_5") (pintype "input+no_connect"))
    )
    (net (code "89") (name "unconnected-(U3-NC-Pad14)") (class "Default")
      (node (ref "U3") (pin "14") (pinfunction "NC_14") (pintype "input+no_connect"))
    )
    (net (code "90") (name "unconnected-(U3-NC-Pad15)") (class "Default")
      (node (ref "U3") (pin "15") (pinfunction "NC_15") (pintype "input+no_connect"))
    )
    (net (code "91") (name "unconnected-(U3-NC-Pad16)") (class "Default")
      (node (ref "U3") (pin "16") (pinfunction "NC_16") (pintype "input+no_connect"))
    )
    (net (code "92") (name "unconnected-(U3-NC-Pad17)") (class "Default")
      (node (ref "U3") (pin "17") (pinfunction "NC_17") (pintype "input+no_connect"))
    )
    (net (code "93") (name "unconnected-(U3-RESV-Pad19)") (class "Default")
      (node (ref "U3") (pin "19") (pinfunction "RESV_19") (pintype "input+no_connect"))
    )
    (net (code "94") (name "unconnected-(U3-RESV-Pad21)") (class "Default")
      (node (ref "U3") (pin "21") (pinfunction "RESV_21") (pintype "input+no_connect"))
    )
    (net (code "95") (name "unconnected-(U3-RESV-Pad22)") (class "Default")
      (node (ref "U3") (pin "22") (pinfunction "RESV_22") (pintype "input+no_connect"))
    )
    (net (code "96") (name "unconnected-(USB1-CC1-PadA5)") (class "Default")
      (node (ref "USB1") (pin "A5") (pinfunction "CC1_A5") (pintype "input+no_connect"))
    )
    (net (code "97") (name "unconnected-(USB1-CC2-PadB5)") (class "Default")
      (node (ref "USB1") (pin "B5") (pinfunction "CC2_B5") (pintype "input+no_connect"))
    )
    (net (code "98") (name "unconnected-(USB1-SUB1-PadA8)") (class "Default")
      (node (ref "USB1") (pin "A8") (pinfunction "SUB1_A8") (pintype "input+no_connect"))
    )
    (net (code "99") (name "unconnected-(USB1-SUB2-PadB8)") (class "Default")
      (node (ref "USB1") (pin "B8") (pinfunction "SUB2_B8") (pintype "input+no_connect"))
    )
  )
)
